# sheet2_power.net
KiCad netlist of a schematic drawn in Altium Designer
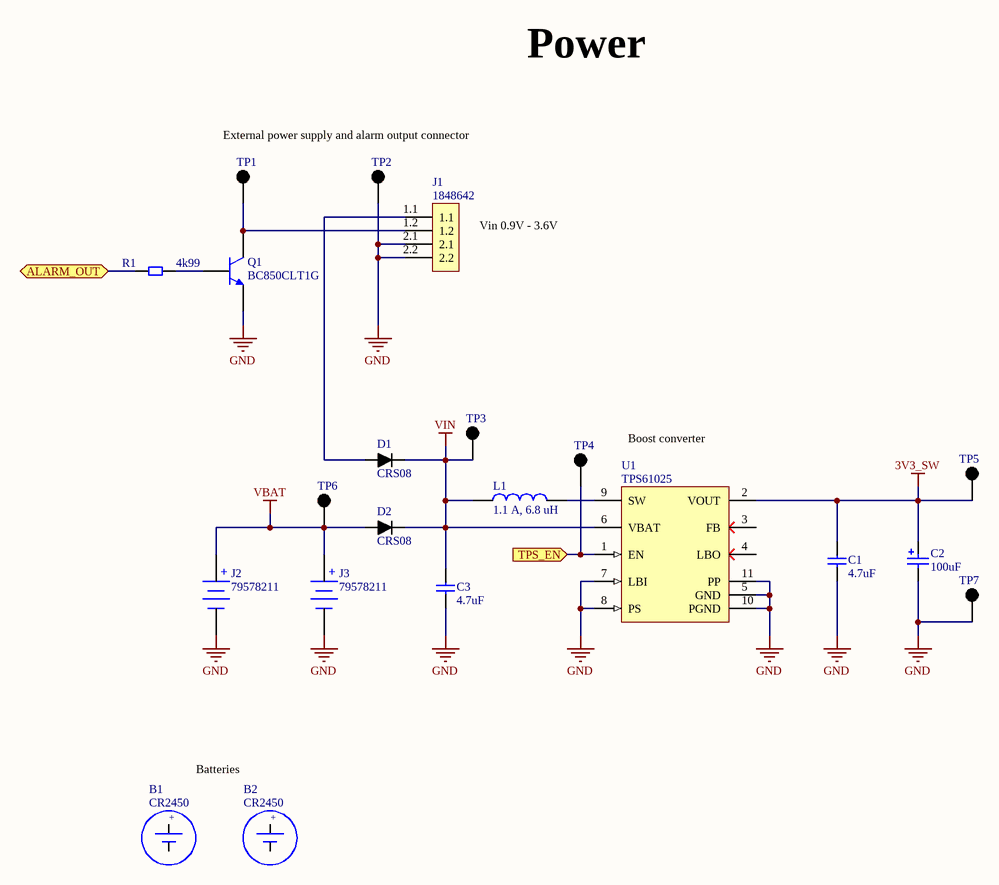
[diagram p0: sheet2_power.SchDoc]

(export (version "E")
  (design (tool "Eeschema 10.0.6"))
  (components
    (comp (ref "B1")
      (value "CR2450")
      (description "CR2450 Coin cell battery")
      (fields (field (name "MANUFACTURER") "Eve Energy"))
      (libsource (lib "Schlib") (part "Battery LCC 2450"))
    )
    (comp (ref "B2")
      (value "CR2450")
      (description "CR2450 Coin cell battery")
      (fields (field (name "MANUFACTURER") "Eve Energy"))
      (libsource (lib "Schlib") (part "Battery LCC 2450"))
    )
    (comp (ref "C1")
      (value "4.7uF")
      (footprint "CAP0603_GR18_MURATA")
      (description "Capacitor X5R 0603 Murata")
      (fields
        (field (name "MANUFACTURER") "Murata")
        (field (name "MANUFACTURER PART NUMBER") "GRM188R60J475KE19D")
      )
      (libsource (lib "Schlib") (part "CAP_0603_4u7"))
    )
    (comp (ref "C2")
      (value "100uF")
      (footprint "WCAP-PSHP_D10mm x L8.7mm")
      (description "WCAP-PSHP Aluminum Polymer Capacitors, D10mm x L8.7mm, 100 uF, 25 VDC")
      (fields
        (field (name "MANUFACTURER PART NUMBER") "875115560004")
        (field (name "MANUFACTURER") "Wurth Elektronik")
        (field (name "PUBLISHER") "Wurth Elektronik")
      )
      (libsource (lib "Schlib") (part "875115560004"))
    )
    (comp (ref "C3")
      (value "4.7uF")
      (footprint "CAP0603_GR18_MURATA")
      (description "Capacitor X5R 0603 Murata")
      (fields
        (field (name "MANUFACTURER") "Murata")
        (field (name "MANUFACTURER PART NUMBER") "GRM188R60J475KE19D")
      )
      (libsource (lib "Schlib") (part "CAP_0603_4u7"))
    )
    (comp (ref "D1")
      (value "CRS08")
      (footprint "SOD-123F")
      (description "CRS08 Schottky Diode")
      (fields (field (name "MANUFACTURER") "Tohsiba"))
      (libsource (lib "Schlib") (part "CRS08 Schottky Diode"))
    )
    (comp (ref "D2")
      (value "CRS08")
      (footprint "SOD-123F")
      (description "CRS08 Schottky Diode")
      (fields (field (name "MANUFACTURER") "Tohsiba"))
      (libsource (lib "Schlib") (part "CRS08 Schottky Diode"))
    )
    (comp (ref "J1")
      (value "1848642")
      (footprint "Phoenix 1848642")
      (description "Plug component, Push-in spring connection")
      (fields (field (name "MANUFACTURER") "Phoenix Contact"))
      (libsource (lib "Schlib") (part "Phoenix Connector"))
    )
    (comp (ref "J2")
      (value "79578211")
      (footprint "79578211")
      (description "Battery Holder WA-BCPH, Battery Type: 2450p")
      (fields (field (name "MANUFACTURER") "Wurth Elektronik") (field (name "PUBLISHER") "Wurth Elektronik"))
      (libsource (lib "Schlib") (part "79578211"))
    )
    (comp (ref "J3")
      (value "79578211")
      (footprint "79578211")
      (description "Battery Holder WA-BCPH, Battery Type: 2450p")
      (fields (field (name "MANUFACTURER") "Wurth Elektronik") (field (name "PUBLISHER") "Wurth Elektronik"))
      (libsource (lib "Schlib") (part "79578211"))
    )
    (comp (ref "L1")
      (value "1.1 A, 6.8 uH")
      (footprint "WE-MAPI_3015")
      (description "WE-MAPI SMD Shielded Power Inductor, size 3015, 1.1 A, 6.8 uH")
      (fields
        (field (name "MANUFACTURER PART NUMBER") "74438335068")
        (field (name "MANUFACTURER") "Wurth Elektronik")
        (field (name "PUBLISHER") "Wurth Elektronik")
      )
      (libsource (lib "Schlib") (part "74438335068"))
    )
    (comp (ref "Q1")
      (value "BC850CLT1G")
      (footprint "SOT23")
      (description "NPN general purpose transistor")
      (fields
        (field (name "MANUFACTURER") "On Semiconductor")
        (field (name "MANUFACTURER PART NUMBER") "NSVBC850CLT1G")
      )
      (libsource (lib "Schlib") (part "BC850C"))
    )
    (comp (ref "R1")
      (value "4k99")
      (footprint "RES0603VISHAY")
      (description "SMD Resistor 4k99 0603")
      (fields
        (field (name "MANUFACTURER") "Vishay")
        (field (name "MANUFACTURER PART NUMBER") "CRCW06034K99FKTABC")
      )
      (libsource (lib "Schlib") (part "Resistor_4k99"))
    )
    (comp (ref "TP1")
      (value "testpad")
      (footprint "TestPad")
      (description "Signal probe pad")
      (libsource (lib "Schlib") (part "TestPad"))
    )
    (comp (ref "TP2")
      (value "testpad")
      (footprint "TestPad")
      (description "Signal probe pad")
      (libsource (lib "Schlib") (part "TestPad"))
    )
    (comp (ref "TP3")
      (value "testpad")
      (footprint "TestPad")
      (description "Signal probe pad")
      (libsource (lib "Schlib") (part "TestPad"))
    )
    (comp (ref "TP4")
      (value "testpad")
      (footprint "TestPad")
      (description "Signal probe pad")
      (libsource (lib "Schlib") (part "TestPad"))
    )
    (comp (ref "TP5")
      (value "testpad")
      (footprint "TestPad")
      (description "Signal probe pad")
      (libsource (lib "Schlib") (part "TestPad"))
    )
    (comp (ref "TP6")
      (value "testpad")
      (footprint "TestPad")
      (description "Signal probe pad")
      (libsource (lib "Schlib") (part "TestPad"))
    )
    (comp (ref "TP7")
      (value "testpad")
      (footprint "TestPad")
      (description "Signal probe pad")
      (libsource (lib "Schlib") (part "TestPad"))
    )
    (comp (ref "U1")
      (value "TPS61025")
      (footprint "DRC10-2400X1650TP")
      (fields
        (field (name "MANUFACTURER") "Texas Instruments")
        (field (name "MANUFACTURER PART NUMBER") "TPS61025DRCR")
      )
      (libsource (lib "Schlib") (part "TPS61025DRCR"))
    )
  )
  (nets
    (net (code "1") (name "/ALARM_OUT") (class "Default")
      (node (ref "R1") (pin "1") (pinfunction "1_1") (pintype "passive"))
    )
    (net (code "2") (name "/TPS_EN") (class "Default")
      (node (ref "TP4") (pin "1") (pinfunction "1_1") (pintype "passive"))
      (node (ref "U1") (pin "1") (pinfunction "EN_1") (pintype "input"))
    )
    (net (code "3") (name "3V3_SW") (class "Default")
      (node (ref "C1") (pin "2") (pinfunction "2_2") (pintype "passive"))
      (node (ref "C2") (pin "1") (pinfunction "P_1") (pintype "passive"))
      (node (ref "TP5") (pin "1") (pinfunction "1_1") (pintype "passive"))
      (node (ref "U1") (pin "2") (pinfunction "VOUT_2") (pintype "power_in"))
    )
    (net (code "4") (name "GND") (class "Default")
      (node (ref "C1") (pin "1") (pinfunction "1_1") (pintype "passive"))
      (node (ref "C2") (pin "2") (pinfunction "N_2") (pintype "passive"))
      (node (ref "C3") (pin "1") (pinfunction "1_1") (pintype "passive"))
      (node (ref "J1") (pin "2.1") (pinfunction "2.1_2.1") (pintype "passive"))
      (node (ref "J1") (pin "2.2") (pinfunction "2.2_2.2") (pintype "passive"))
      (node (ref "J2") (pin "2") (pinfunction "Neg_2") (pintype "passive"))
      (node (ref "J3") (pin "2") (pinfunction "Neg_2") (pintype "passive"))
      (node (ref "Q1") (pin "3") (pinfunction "3_3") (pintype "passive"))
      (node (ref "TP2") (pin "1") (pinfunction "1_1") (pintype "passive"))
      (node (ref "TP7") (pin "1") (pinfunction "1_1") (pintype "passive"))
      (node (ref "U1") (pin "10") (pinfunction "PGND_10") (pintype "power_in"))
      (node (ref "U1") (pin "11") (pinfunction "PP_11") (pintype "power_in"))
      (node (ref "U1") (pin "5") (pinfunction "GND_5") (pintype "power_in"))
      (node (ref "U1") (pin "7") (pinfunction "LBI_7") (pintype "input"))
      (node (ref "U1") (pin "8") (pinfunction "PS_8") (pintype "input"))
    )
    (net (code "5") (name "Net-(D1-PadA)") (class "Default")
      (node (ref "D1") (pin "A") (pinfunction "A_A") (pintype "passive"))
      (node (ref "J1") (pin "1.1") (pinfunction "1.1_1.1") (pintype "passive"))
    )
    (net (code "6") (name "Net-(J1-Pad1.2)") (class "Default")
      (node (ref "J1") (pin "1.2") (pinfunction "1.2_1.2") (pintype "passive"))
      (node (ref "Q1") (pin "1") (pinfunction "1_1") (pintype "passive"))
      (node (ref "TP1") (pin "1") (pinfunction "1_1") (pintype "passive"))
    )
    (net (code "7") (name "Net-(Q1-Pad2)") (class "Default")
      (node (ref "Q1") (pin "2") (pinfunction "2_2") (pintype "passive"))
      (node (ref "R1") (pin "2") (pinfunction "2_2") (pintype "passive"))
    )
    (net (code "8") (name "Net-(U1-SW)") (class "Default")
      (node (ref "L1") (pin "2") (pinfunction "2_2") (pintype "passive"))
      (node (ref "U1") (pin "9") (pinfunction "SW_9") (pintype "power_in"))
    )
    (net (code "9") (name "VBAT") (class "Default")
      (node (ref "D2") (pin "A") (pinfunction "A_A") (pintype "passive"))
      (node (ref "J2") (pin "1") (pinfunction "Pos_1") (pintype "passive"))
      (node (ref "J3") (pin "1") (pinfunction "Pos_1") (pintype "passive"))
      (node (ref "TP6") (pin "1") (pinfunction "1_1") (pintype "passive"))
    )
    (net (code "10") (name "VIN") (class "Default")
      (node (ref "C3") (pin "2") (pinfunction "2_2") (pintype "passive"))
      (node (ref "D1") (pin "C") (pinfunction "C_C") (pintype "passive"))
      (node (ref "D2") (pin "C") (pinfunction "C_C") (pintype "passive"))
      (node (ref "L1") (pin "1") (pinfunction "1_1") (pintype "passive"))
      (node (ref "TP3") (pin "1") (pinfunction "1_1") (pintype "passive"))
      (node (ref "U1") (pin "6") (pinfunction "VBAT_6") (pintype "power_in"))
    )
    (net (code "11") (name "unconnected-(U1-FB-Pad3)") (class "Default")
      (node (ref "U1") (pin "3") (pinfunction "FB_3") (pintype "passive"))
    )
    (net (code "12") (name "unconnected-(U1-LBO-Pad4)") (class "Default")
      (node (ref "U1") (pin "4") (pinfunction "LBO_4") (pintype "tri_state"))
    )
  )
)
